# OLED_64x32.net
KiCad netlist of a schematic drawn in EAGLE
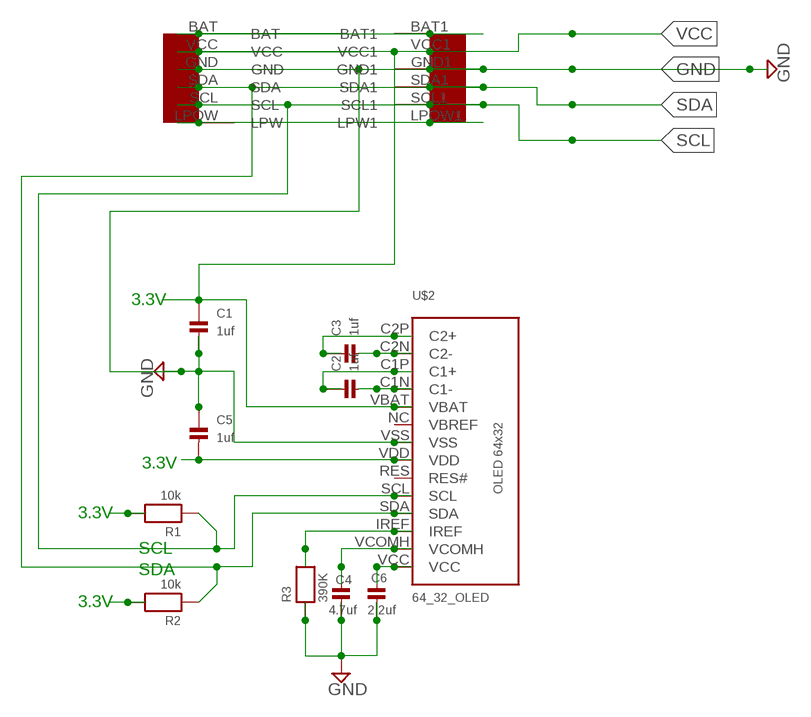
[diagram p0: schematic, sheet 1]

(export (version "E")
  (design (tool "Eeschema 10.0.6"))
  (components
    (comp (ref "C1")
      (value "1uf")
      (footprint "eagle-import:0603")
      (libsource (lib "eagle-import") (part "CAP_CERAMIC0603"))
    )
    (comp (ref "C2")
      (value "1uf")
      (footprint "eagle-import:0603")
      (libsource (lib "eagle-import") (part "CAP_CERAMIC0603"))
    )
    (comp (ref "C3")
      (value "1uf")
      (footprint "eagle-import:0603")
      (libsource (lib "eagle-import") (part "CAP_CERAMIC0603"))
    )
    (comp (ref "C4")
      (value "4.7uf")
      (footprint "eagle-import:0603")
      (libsource (lib "eagle-import") (part "CAP_CERAMIC0603"))
    )
    (comp (ref "C5")
      (value "1uf")
      (footprint "eagle-import:0603")
      (libsource (lib "eagle-import") (part "CAP_CERAMIC0603"))
    )
    (comp (ref "C6")
      (value "2.2uf")
      (footprint "eagle-import:0603")
      (libsource (lib "eagle-import") (part "CAP_CERAMIC0603"))
    )
    (comp (ref "R1")
      (value "10k")
      (footprint "eagle-import:0603")
      (libsource (lib "eagle-import") (part "RESISTOR0603"))
    )
    (comp (ref "R2")
      (value "10k")
      (footprint "eagle-import:0603")
      (libsource (lib "eagle-import") (part "RESISTOR0603"))
    )
    (comp (ref "R3")
      (value "390K")
      (footprint "eagle-import:0603")
      (libsource (lib "eagle-import") (part "RESISTOR0603"))
    )
    (comp (ref "U$1")
      (value "EASYI2C6PINHEADERBLE_VERSION")
      (footprint "eagle-import:EASYI2C6HEADERBLE")
      (libsource (lib "eagle-import") (part "EASYI2C6PINHEADERBLE_VERSION"))
    )
    (comp (ref "U$2")
      (value "64_32_OLED")
      (footprint "eagle-import:64_32_OLED")
      (libsource (lib "eagle-import") (part "64_32_OLED"))
    )
  )
  (nets
    (net (code "1") (name "GND") (class "Default")
      (node (ref "C1") (pin "2") (pinfunction "P$2_2") (pintype "passive"))
      (node (ref "C4") (pin "2") (pinfunction "P$2_2") (pintype "passive"))
      (node (ref "C5") (pin "1") (pinfunction "P$1_1") (pintype "passive"))
      (node (ref "C6") (pin "2") (pinfunction "P$2_2") (pintype "passive"))
      (node (ref "R3") (pin "1") (pinfunction "1_1") (pintype "passive"))
      (node (ref "U$1") (pin "GND") (pinfunction "GND_GND") (pintype "bidirectional"))
      (node (ref "U$1") (pin "GND1") (pinfunction "GND1_GND1") (pintype "bidirectional"))
      (node (ref "U$2") (pin "VSS") (pinfunction "VSS_VSS") (pintype "bidirectional"))
    )
    (net (code "2") (name "Net-(C2-P$1)") (class "Default")
      (node (ref "C2") (pin "1") (pinfunction "P$1_1") (pintype "passive"))
      (node (ref "U$2") (pin "C1P") (pinfunction "C1+_C1P") (pintype "bidirectional"))
    )
    (net (code "3") (name "Net-(C2-P$2)") (class "Default")
      (node (ref "C2") (pin "2") (pinfunction "P$2_2") (pintype "passive"))
      (node (ref "U$2") (pin "C1N") (pinfunction "C1-_C1N") (pintype "bidirectional"))
    )
    (net (code "4") (name "Net-(C3-P$1)") (class "Default")
      (node (ref "C3") (pin "1") (pinfunction "P$1_1") (pintype "passive"))
      (node (ref "U$2") (pin "C2P") (pinfunction "C2+_C2P") (pintype "bidirectional"))
    )
    (net (code "5") (name "Net-(C3-P$2)") (class "Default")
      (node (ref "C3") (pin "2") (pinfunction "P$2_2") (pintype "passive"))
      (node (ref "U$2") (pin "C2N") (pinfunction "C2-_C2N") (pintype "bidirectional"))
    )
    (net (code "6") (name "Net-(C4-P$1)") (class "Default")
      (node (ref "C4") (pin "1") (pinfunction "P$1_1") (pintype "passive"))
      (node (ref "U$2") (pin "VCOMH") (pinfunction "VCOMH_VCOMH") (pintype "bidirectional"))
    )
    (net (code "7") (name "Net-(C6-P$1)") (class "Default")
      (node (ref "C6") (pin "1") (pinfunction "P$1_1") (pintype "passive"))
      (node (ref "U$2") (pin "VCC") (pinfunction "VCC_VCC") (pintype "bidirectional"))
    )
    (net (code "8") (name "Net-(R3-Pad2)") (class "Default")
      (node (ref "R3") (pin "2") (pinfunction "2_2") (pintype "passive"))
      (node (ref "U$2") (pin "IREF") (pinfunction "IREF_IREF") (pintype "bidirectional"))
    )
    (net (code "9") (name "Net-(U$1-LPW)") (class "Default")
      (node (ref "U$1") (pin "LPOW") (pinfunction "LPW_LPOW") (pintype "bidirectional"))
      (node (ref "U$1") (pin "LPOW1") (pinfunction "LPW1_LPOW1") (pintype "bidirectional"))
    )
    (net (code "10") (name "Net-(U$1-PadBAT)") (class "Default")
      (node (ref "U$1") (pin "BAT") (pinfunction "BAT_BAT") (pintype "bidirectional"))
      (node (ref "U$1") (pin "BAT1") (pinfunction "BAT1_BAT1") (pintype "bidirectional"))
    )
    (net (code "11") (name "SCL") (class "Default")
      (node (ref "R1") (pin "1") (pinfunction "1_1") (pintype "passive"))
      (node (ref "U$1") (pin "SCL") (pinfunction "SCL_SCL") (pintype "bidirectional"))
      (node (ref "U$1") (pin "SCL1") (pinfunction "SCL1_SCL1") (pintype "bidirectional"))
      (node (ref "U$2") (pin "SCL") (pinfunction "SCL_SCL") (pintype "bidirectional"))
    )
    (net (code "12") (name "SDA") (class "Default")
      (node (ref "R2") (pin "1") (pinfunction "1_1") (pintype "passive"))
      (node (ref "U$1") (pin "SDA") (pinfunction "SDA_SDA") (pintype "bidirectional"))
      (node (ref "U$1") (pin "SDA1") (pinfunction "SDA1_SDA1") (pintype "bidirectional"))
      (node (ref "U$2") (pin "SDA") (pinfunction "SDA_SDA") (pintype "bidirectional"))
    )
    (net (code "13") (name "VCC") (class "Default")
      (node (ref "C1") (pin "1") (pinfunction "P$1_1") (pintype "passive"))
      (node (ref "C5") (pin "2") (pinfunction "P$2_2") (pintype "passive"))
      (node (ref "R1") (pin "2") (pinfunction "2_2") (pintype "passive"))
      (node (ref "R2") (pin "2") (pinfunction "2_2") (pintype "passive"))
      (node (ref "U$1") (pin "VCC") (pinfunction "VCC_VCC") (pintype "bidirectional"))
      (node (ref "U$1") (pin "VCC1") (pinfunction "VCC1_VCC1") (pintype "bidirectional"))
      (node (ref "U$2") (pin "VBAT") (pinfunction "VBAT_VBAT") (pintype "bidirectional"))
      (node (ref "U$2") (pin "VDD") (pinfunction "VDD_VDD") (pintype "bidirectional"))
    )
    (net (code "14") (name "unconnected-(U$2-RES#-PadRES)") (class "Default")
      (node (ref "U$2") (pin "RES") (pinfunction "RES#_RES") (pintype "bidirectional"))
    )
    (net (code "15") (name "unconnected-(U$2-VBREF-PadNC)") (class "Default")
      (node (ref "U$2") (pin "NC") (pinfunction "VBREF_NC") (pintype "bidirectional"))
    )
  )
)
